# TIA_For_Photodiode.net
KiCad netlist of a schematic drawn in Altium Designer
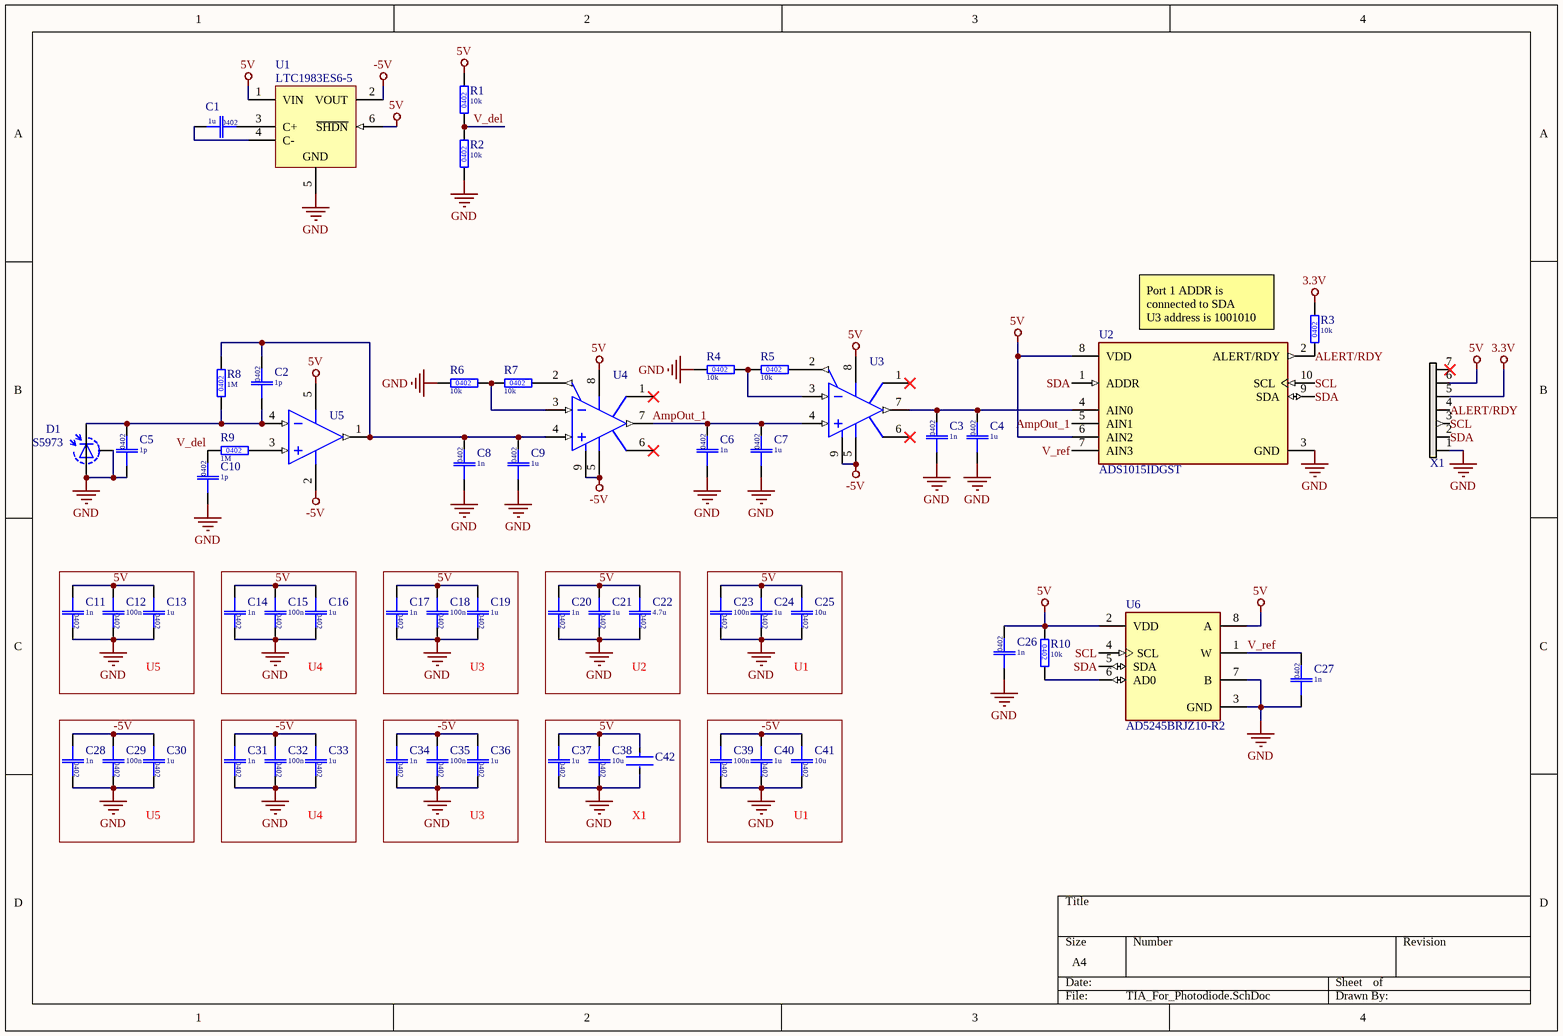
[diagram p0: TIA_For_Photodiode.SchDoc]

(export (version "E")
  (design (tool "Eeschema 10.0.6"))
  (components
    (comp (ref "C1")
      (value "1u")
      (footprint "SMD 0402")
      (fields (field (name "TOLERANCE") "10%") (field (name "VOLTAGE") "25v"))
      (libsource (lib "ComponentsDatabase") (part "Capacitor 0402"))
    )
    (comp (ref "C2")
      (value "1p")
      (footprint "SMD 0402")
      (fields (field (name "TOLERANCE") "20%") (field (name "VOLTAGE") "6,3v"))
      (libsource (lib "ComponentsDatabase") (part "Capacitor 0402"))
    )
    (comp (ref "C3")
      (value "1n")
      (footprint "SMD 0402")
      (fields (field (name "TOLERANCE") "20%") (field (name "VOLTAGE") "6,3v"))
      (libsource (lib "ComponentsDatabase") (part "Capacitor 0402"))
    )
    (comp (ref "C4")
      (value "1u")
      (footprint "SMD 0402")
      (fields (field (name "TOLERANCE") "20%") (field (name "VOLTAGE") "6,3v"))
      (libsource (lib "ComponentsDatabase") (part "Capacitor 0402"))
    )
    (comp (ref "C5")
      (value "1p")
      (footprint "SMD 0402")
      (fields (field (name "TOLERANCE") "20%") (field (name "VOLTAGE") "6,3v"))
      (libsource (lib "ComponentsDatabase") (part "Capacitor 0402"))
    )
    (comp (ref "C6")
      (value "1n")
      (footprint "SMD 0402")
      (fields (field (name "TOLERANCE") "20%") (field (name "VOLTAGE") "6,3v"))
      (libsource (lib "ComponentsDatabase") (part "Capacitor 0402"))
    )
    (comp (ref "C7")
      (value "1u")
      (footprint "SMD 0402")
      (fields (field (name "TOLERANCE") "20%") (field (name "VOLTAGE") "6,3v"))
      (libsource (lib "ComponentsDatabase") (part "Capacitor 0402"))
    )
    (comp (ref "C8")
      (value "1n")
      (footprint "SMD 0402")
      (fields (field (name "TOLERANCE") "20%") (field (name "VOLTAGE") "6,3v"))
      (libsource (lib "ComponentsDatabase") (part "Capacitor 0402"))
    )
    (comp (ref "C9")
      (value "1u")
      (footprint "SMD 0402")
      (fields (field (name "TOLERANCE") "20%") (field (name "VOLTAGE") "6,3v"))
      (libsource (lib "ComponentsDatabase") (part "Capacitor 0402"))
    )
    (comp (ref "C10")
      (value "1p")
      (footprint "SMD 0402")
      (fields (field (name "TOLERANCE") "20%") (field (name "VOLTAGE") "6,3v"))
      (libsource (lib "ComponentsDatabase") (part "Capacitor 0402"))
    )
    (comp (ref "C11")
      (value "1n")
      (footprint "SMD 0402")
      (fields (field (name "TOLERANCE") "20%") (field (name "VOLTAGE") "6,3v"))
      (libsource (lib "ComponentsDatabase") (part "Capacitor 0402"))
    )
    (comp (ref "C12")
      (value "100n")
      (footprint "SMD 0402")
      (fields (field (name "TOLERANCE") "20%") (field (name "VOLTAGE") "6,3v"))
      (libsource (lib "ComponentsDatabase") (part "Capacitor 0402"))
    )
    (comp (ref "C13")
      (value "1u")
      (footprint "SMD 0402")
      (fields (field (name "TOLERANCE") "20%") (field (name "VOLTAGE") "6,3v"))
      (libsource (lib "ComponentsDatabase") (part "Capacitor 0402"))
    )
    (comp (ref "C14")
      (value "1n")
      (footprint "SMD 0402")
      (fields (field (name "TOLERANCE") "20%") (field (name "VOLTAGE") "6,3v"))
      (libsource (lib "ComponentsDatabase") (part "Capacitor 0402"))
    )
    (comp (ref "C15")
      (value "100n")
      (footprint "SMD 0402")
      (fields (field (name "TOLERANCE") "20%") (field (name "VOLTAGE") "6,3v"))
      (libsource (lib "ComponentsDatabase") (part "Capacitor 0402"))
    )
    (comp (ref "C16")
      (value "1u")
      (footprint "SMD 0402")
      (fields (field (name "TOLERANCE") "20%") (field (name "VOLTAGE") "6,3v"))
      (libsource (lib "ComponentsDatabase") (part "Capacitor 0402"))
    )
    (comp (ref "C17")
      (value "1n")
      (footprint "SMD 0402")
      (fields (field (name "TOLERANCE") "20%") (field (name "VOLTAGE") "6,3v"))
      (libsource (lib "ComponentsDatabase") (part "Capacitor 0402"))
    )
    (comp (ref "C18")
      (value "100n")
      (footprint "SMD 0402")
      (fields (field (name "TOLERANCE") "20%") (field (name "VOLTAGE") "6,3v"))
      (libsource (lib "ComponentsDatabase") (part "Capacitor 0402"))
    )
    (comp (ref "C19")
      (value "1u")
      (footprint "SMD 0402")
      (fields (field (name "TOLERANCE") "20%") (field (name "VOLTAGE") "6,3v"))
      (libsource (lib "ComponentsDatabase") (part "Capacitor 0402"))
    )
    (comp (ref "C20")
      (value "1n")
      (footprint "SMD 0402")
      (fields (field (name "TOLERANCE") "20%") (field (name "VOLTAGE") "6,3v"))
      (libsource (lib "ComponentsDatabase") (part "Capacitor 0402"))
    )
    (comp (ref "C21")
      (value "1u")
      (footprint "SMD 0402")
      (fields (field (name "TOLERANCE") "20%") (field (name "VOLTAGE") "6,3v"))
      (libsource (lib "ComponentsDatabase") (part "Capacitor 0402"))
    )
    (comp (ref "C22")
      (value "4.7u")
      (footprint "SMD 0402")
      (fields (field (name "TOLERANCE") "20%") (field (name "VOLTAGE") "6,3v"))
      (libsource (lib "ComponentsDatabase") (part "Capacitor 0402"))
    )
    (comp (ref "C23")
      (value "100n")
      (footprint "SMD 0402")
      (fields (field (name "TOLERANCE") "20%") (field (name "VOLTAGE") "6,3v"))
      (libsource (lib "ComponentsDatabase") (part "Capacitor 0402"))
    )
    (comp (ref "C24")
      (value "1u")
      (footprint "SMD 0402")
      (fields (field (name "TOLERANCE") "20%") (field (name "VOLTAGE") "6,3v"))
      (libsource (lib "ComponentsDatabase") (part "Capacitor 0402"))
    )
    (comp (ref "C25")
      (value "10u")
      (footprint "SMD 0402")
      (fields (field (name "TOLERANCE") "20%") (field (name "VOLTAGE") "6,3v"))
      (libsource (lib "ComponentsDatabase") (part "Capacitor 0402"))
    )
    (comp (ref "C26")
      (value "1n")
      (footprint "SMD 0402")
      (fields (field (name "TOLERANCE") "20%") (field (name "VOLTAGE") "6,3v"))
      (libsource (lib "ComponentsDatabase") (part "Capacitor 0402"))
    )
    (comp (ref "C27")
      (value "1n")
      (footprint "SMD 0402")
      (fields (field (name "TOLERANCE") "20%") (field (name "VOLTAGE") "6,3v"))
      (libsource (lib "ComponentsDatabase") (part "Capacitor 0402"))
    )
    (comp (ref "C28")
      (value "1n")
      (footprint "SMD 0402")
      (fields (field (name "TOLERANCE") "20%") (field (name "VOLTAGE") "6,3v"))
      (libsource (lib "ComponentsDatabase") (part "Capacitor 0402"))
    )
    (comp (ref "C29")
      (value "100n")
      (footprint "SMD 0402")
      (fields (field (name "TOLERANCE") "20%") (field (name "VOLTAGE") "6,3v"))
      (libsource (lib "ComponentsDatabase") (part "Capacitor 0402"))
    )
    (comp (ref "C30")
      (value "1u")
      (footprint "SMD 0402")
      (fields (field (name "TOLERANCE") "20%") (field (name "VOLTAGE") "6,3v"))
      (libsource (lib "ComponentsDatabase") (part "Capacitor 0402"))
    )
    (comp (ref "C31")
      (value "1n")
      (footprint "SMD 0402")
      (fields (field (name "TOLERANCE") "20%") (field (name "VOLTAGE") "6,3v"))
      (libsource (lib "ComponentsDatabase") (part "Capacitor 0402"))
    )
    (comp (ref "C32")
      (value "100n")
      (footprint "SMD 0402")
      (fields (field (name "TOLERANCE") "20%") (field (name "VOLTAGE") "6,3v"))
      (libsource (lib "ComponentsDatabase") (part "Capacitor 0402"))
    )
    (comp (ref "C33")
      (value "1u")
      (footprint "SMD 0402")
      (fields (field (name "TOLERANCE") "20%") (field (name "VOLTAGE") "6,3v"))
      (libsource (lib "ComponentsDatabase") (part "Capacitor 0402"))
    )
    (comp (ref "C34")
      (value "1n")
      (footprint "SMD 0402")
      (fields (field (name "TOLERANCE") "20%") (field (name "VOLTAGE") "6,3v"))
      (libsource (lib "ComponentsDatabase") (part "Capacitor 0402"))
    )
    (comp (ref "C35")
      (value "100n")
      (footprint "SMD 0402")
      (fields (field (name "TOLERANCE") "20%") (field (name "VOLTAGE") "6,3v"))
      (libsource (lib "ComponentsDatabase") (part "Capacitor 0402"))
    )
    (comp (ref "C36")
      (value "1u")
      (footprint "SMD 0402")
      (fields (field (name "TOLERANCE") "20%") (field (name "VOLTAGE") "6,3v"))
      (libsource (lib "ComponentsDatabase") (part "Capacitor 0402"))
    )
    (comp (ref "C37")
      (value "1u")
      (footprint "SMD 0402")
      (fields (field (name "TOLERANCE") "20%") (field (name "VOLTAGE") "6,3v"))
      (libsource (lib "ComponentsDatabase") (part "Capacitor 0402"))
    )
    (comp (ref "C38")
      (value "10u")
      (footprint "SMD 0402")
      (fields (field (name "TOLERANCE") "20%") (field (name "VOLTAGE") "6,3v"))
      (libsource (lib "ComponentsDatabase") (part "Capacitor 0402"))
    )
    (comp (ref "C39")
      (value "100n")
      (footprint "SMD 0402")
      (fields (field (name "TOLERANCE") "20%") (field (name "VOLTAGE") "6,3v"))
      (libsource (lib "ComponentsDatabase") (part "Capacitor 0402"))
    )
    (comp (ref "C40")
      (value "1u")
      (footprint "SMD 0402")
      (fields (field (name "TOLERANCE") "20%") (field (name "VOLTAGE") "6,3v"))
      (libsource (lib "ComponentsDatabase") (part "Capacitor 0402"))
    )
    (comp (ref "C41")
      (value "10u")
      (footprint "SMD 0402")
      (fields (field (name "TOLERANCE") "20%") (field (name "VOLTAGE") "6,3v"))
      (libsource (lib "ComponentsDatabase") (part "Capacitor 0402"))
    )
    (comp (ref "C42")
      (value "GRM32ER60J107ME20L")
      (footprint "FP-GRM32-0_3-MFG")
      (description "CAP CER 100UF 6.3V X5R 1210")
      (fields
        (field (name "OCTOPART") "https://octopart.com/grm32er60j107me20l-murata-197007")
        (field (name "3DS PART NUMBER") "220-00002")
      )
      (libsource (lib "Altium Content Vault") (part "11868f565c42a9108669ba33697ecf6"))
    )
    (comp (ref "D1")
      (value "S5973")
      (footprint "TO-18")
      (description "Hamamatsu, S5973 IR + Visible Light Si PIN Photodiode, Through Hole TO-18")
      (libsource (lib "ShematicLIB") (part "S5973"))
    )
    (comp (ref "R1")
      (value "10k")
      (footprint "SMD 0402")
      (fields (field (name "TOLERANCE") "1%"))
      (libsource (lib "ComponentsDatabase") (part "Resistor 0402"))
    )
    (comp (ref "R2")
      (value "10k")
      (footprint "SMD 0402")
      (fields (field (name "TOLERANCE") "1%"))
      (libsource (lib "ComponentsDatabase") (part "Resistor 0402"))
    )
    (comp (ref "R3")
      (value "10k")
      (footprint "SMD 0402")
      (fields (field (name "TOLERANCE") "1%"))
      (libsource (lib "ComponentsDatabase") (part "Resistor 0402"))
    )
    (comp (ref "R4")
      (value "10k")
      (footprint "SMD 0402")
      (fields (field (name "TOLERANCE") "1%"))
      (libsource (lib "ComponentsDatabase") (part "Resistor 0402"))
    )
    (comp (ref "R5")
      (value "10k")
      (footprint "SMD 0402")
      (fields (field (name "TOLERANCE") "1%"))
      (libsource (lib "ComponentsDatabase") (part "Resistor 0402"))
    )
    (comp (ref "R6")
      (value "10k")
      (footprint "SMD 0402")
      (fields (field (name "TOLERANCE") "1%"))
      (libsource (lib "ComponentsDatabase") (part "Resistor 0402"))
    )
    (comp (ref "R7")
      (value "10k")
      (footprint "SMD 0402")
      (fields (field (name "TOLERANCE") "1%"))
      (libsource (lib "ComponentsDatabase") (part "Resistor 0402"))
    )
    (comp (ref "R8")
      (value "1M")
      (footprint "SMD 0402")
      (fields (field (name "TOLERANCE") "1%"))
      (libsource (lib "ComponentsDatabase") (part "Resistor 0402"))
    )
    (comp (ref "R9")
      (value "1M")
      (footprint "SMD 0402")
      (fields (field (name "TOLERANCE") "1%"))
      (libsource (lib "ComponentsDatabase") (part "Resistor 0402"))
    )
    (comp (ref "R10")
      (value "10k")
      (footprint "SMD 0402")
      (fields (field (name "TOLERANCE") "1%"))
      (libsource (lib "ComponentsDatabase") (part "Resistor 0402"))
    )
    (comp (ref "U1")
      (value "LTC1983ES6-5")
      (footprint "LT-S6-6-TSOT-23_M")
      (fields (field (name "MANUFACTURER") "Linear Technology"))
      (libsource (lib "Altium Content Vault") (part "LT-LTC1983-S6-6"))
    )
    (comp (ref "U2")
      (value "ADS1015IDGST")
      (footprint "FP-DGS0010A-MFG")
      (description "IC ADC 12BIT SIGMA-DELTA 10VSSOP")
      (libsource (lib "Altium Content Vault") (part "0fb225032f4bd54fd540a872e776a50"))
    )
    (comp (ref "U3")
      (value "AD8045ACPZ-REEL7")
      (footprint "ADI-CP-8-2_N")
      (fields (field (name "GENERIC PART NUMBER") "AD8045") (field (name "MANUFACTURER") "Analog Devices"))
      (libsource (lib "Altium Content Vault") (part "ADI-AD8045-CP-8-2"))
    )
    (comp (ref "U4")
      (value "AD8045ACPZ-REEL7")
      (footprint "ADI-CP-8-2_N")
      (fields (field (name "GENERIC PART NUMBER") "AD8045") (field (name "MANUFACTURER") "Analog Devices"))
      (libsource (lib "Altium Content Vault") (part "ADI-AD8045-CP-8-2"))
    )
    (comp (ref "U5")
      (value "AD8065ARTZ-REEL7")
      (footprint "ADI-RJ-5_L")
      (fields (field (name "GENERIC PART NUMBER") "AD8065") (field (name "MANUFACTURER") "Analog Devices"))
      (libsource (lib "Altium Content Vault") (part "ADI-AD80XX-5"))
    )
    (comp (ref "U6")
      (value "AD5245BRJZ10-R2")
      (footprint "FP-RJ-8-IPC_C")
      (description "IC DGT POT 10KOHM 256TAP SOT23-8")
      (fields (field (name "TOLERANCE") "30%") (field (name "MANUFACTURER") "Analog Devices"))
      (libsource (lib "Altium Content Vault") (part "8d408c839f24318d0976f3536df8182"))
    )
    (comp (ref "X1")
      (value "PicoBlade 7 pins")
      (footprint "PicoBlade 7 pins")
      (libsource (lib "ShematicLIB") (part "PicoBlade 7 pins"))
    )
  )
  (nets
    (net (code "1") (name "-5V") (class "Default")
      (node (ref "C28") (pin "1") (pinfunction "1_1") (pintype "passive"))
      (node (ref "C29") (pin "1") (pinfunction "1_1") (pintype "passive"))
      (node (ref "C30") (pin "1") (pinfunction "1_1") (pintype "passive"))
      (node (ref "C31") (pin "1") (pinfunction "1_1") (pintype "passive"))
      (node (ref "C32") (pin "1") (pinfunction "1_1") (pintype "passive"))
      (node (ref "C33") (pin "1") (pinfunction "1_1") (pintype "passive"))
      (node (ref "C34") (pin "1") (pinfunction "1_1") (pintype "passive"))
      (node (ref "C35") (pin "1") (pinfunction "1_1") (pintype "passive"))
      (node (ref "C36") (pin "1") (pinfunction "1_1") (pintype "passive"))
      (node (ref "C39") (pin "1") (pinfunction "1_1") (pintype "passive"))
      (node (ref "C40") (pin "1") (pinfunction "1_1") (pintype "passive"))
      (node (ref "C41") (pin "1") (pinfunction "1_1") (pintype "passive"))
      (node (ref "U1") (pin "2") (pinfunction "VOUT_2") (pintype "power_in"))
      (node (ref "U3") (pin "5") (pinfunction "-VS_5") (pintype "power_in"))
      (node (ref "U3") (pin "9") (pinfunction "EP_9") (pintype "power_in"))
      (node (ref "U4") (pin "5") (pinfunction "-VS_5") (pintype "power_in"))
      (node (ref "U4") (pin "9") (pinfunction "EP_9") (pintype "power_in"))
      (node (ref "U5") (pin "2") (pinfunction "-VS_2") (pintype "power_in"))
    )
    (net (code "2") (name "/ALERT{slash}RDY") (class "Default")
      (node (ref "R3") (pin "1") (pinfunction "1_1") (pintype "passive"))
      (node (ref "U2") (pin "2") (pinfunction "ALERT/RDY_2") (pintype "output"))
      (node (ref "X1") (pin "4") (pinfunction "4_4") (pintype "passive"))
    )
    (net (code "3") (name "/AmpOut_1") (class "Default")
      (node (ref "C6") (pin "2") (pinfunction "2_2") (pintype "passive"))
      (node (ref "C7") (pin "2") (pinfunction "2_2") (pintype "passive"))
      (node (ref "U2") (pin "5") (pinfunction "AIN1_5") (pintype "passive"))
      (node (ref "U3") (pin "4") (pinfunction "+IN_4") (pintype "input"))
      (node (ref "U4") (pin "7") (pinfunction "OUT_7") (pintype "output"))
    )
    (net (code "4") (name "/SCL") (class "Default")
      (node (ref "U2") (pin "10") (pinfunction "SCL_10") (pintype "input"))
      (node (ref "U6") (pin "4") (pinfunction "SCL_4") (pintype "input"))
      (node (ref "X1") (pin "3") (pinfunction "3_3") (pintype "output"))
    )
    (net (code "5") (name "/SDA") (class "Default")
      (node (ref "U2") (pin "1") (pinfunction "ADDR_1") (pintype "input"))
      (node (ref "U2") (pin "9") (pinfunction "SDA_9") (pintype "bidirectional"))
      (node (ref "U6") (pin "5") (pinfunction "SDA_5") (pintype "bidirectional"))
      (node (ref "X1") (pin "2") (pinfunction "2_2") (pintype "passive"))
    )
    (net (code "6") (name "/V_del") (class "Default")
      (node (ref "C10") (pin "2") (pinfunction "2_2") (pintype "passive"))
      (node (ref "R1") (pin "1") (pinfunction "1_1") (pintype "passive"))
      (node (ref "R2") (pin "2") (pinfunction "2_2") (pintype "passive"))
      (node (ref "R9") (pin "1") (pinfunction "1_1") (pintype "passive"))
    )
    (net (code "7") (name "/V_ref") (class "Default")
      (node (ref "C27") (pin "2") (pinfunction "2_2") (pintype "passive"))
      (node (ref "U2") (pin "7") (pinfunction "AIN3_7") (pintype "passive"))
      (node (ref "U6") (pin "1") (pinfunction "W_1") (pintype "passive"))
    )
    (net (code "8") (name "3.3V") (class "Default")
      (node (ref "R3") (pin "2") (pinfunction "2_2") (pintype "passive"))
      (node (ref "X1") (pin "5") (pinfunction "5_5") (pintype "passive"))
    )
    (net (code "9") (name "5V") (class "Default")
      (node (ref "C11") (pin "1") (pinfunction "1_1") (pintype "passive"))
      (node (ref "C12") (pin "1") (pinfunction "1_1") (pintype "passive"))
      (node (ref "C13") (pin "1") (pinfunction "1_1") (pintype "passive"))
      (node (ref "C14") (pin "1") (pinfunction "1_1") (pintype "passive"))
      (node (ref "C15") (pin "1") (pinfunction "1_1") (pintype "passive"))
      (node (ref "C16") (pin "1") (pinfunction "1_1") (pintype "passive"))
      (node (ref "C17") (pin "1") (pinfunction "1_1") (pintype "passive"))
      (node (ref "C18") (pin "1") (pinfunction "1_1") (pintype "passive"))
      (node (ref "C19") (pin "1") (pinfunction "1_1") (pintype "passive"))
      (node (ref "C20") (pin "1") (pinfunction "1_1") (pintype "passive"))
      (node (ref "C21") (pin "1") (pinfunction "1_1") (pintype "passive"))
      (node (ref "C22") (pin "1") (pinfunction "1_1") (pintype "passive"))
      (node (ref "C23") (pin "1") (pinfunction "1_1") (pintype "passive"))
      (node (ref "C24") (pin "1") (pinfunction "1_1") (pintype "passive"))
      (node (ref "C25") (pin "1") (pinfunction "1_1") (pintype "passive"))
      (node (ref "C26") (pin "2") (pinfunction "2_2") (pintype "passive"))
      (node (ref "C37") (pin "1") (pinfunction "1_1") (pintype "passive"))
      (node (ref "C38") (pin "1") (pinfunction "1_1") (pintype "passive"))
      (node (ref "C42") (pin "1") (pinfunction "1_1") (pintype "passive"))
      (node (ref "R1") (pin "2") (pinfunction "2_2") (pintype "passive"))
      (node (ref "R10") (pin "1") (pinfunction "1_1") (pintype "passive"))
      (node (ref "U1") (pin "1") (pinfunction "VIN_1") (pintype "power_in"))
      (node (ref "U1") (pin "6") (pinfunction "~{SHDN}_6") (pintype "input"))
      (node (ref "U2") (pin "6") (pinfunction "AIN2_6") (pintype "passive"))
      (node (ref "U2") (pin "8") (pinfunction "VDD_8") (pintype "power_in"))
      (node (ref "U3") (pin "8") (pinfunction "+VS_8") (pintype "power_in"))
      (node (ref "U4") (pin "8") (pinfunction "+VS_8") (pintype "power_in"))
      (node (ref "U5") (pin "5") (pinfunction "+VS_5") (pintype "power_in"))
      (node (ref "U6") (pin "2") (pinfunction "VDD_2") (pintype "power_in"))
      (node (ref "U6") (pin "8") (pinfunction "A_8") (pintype "passive"))
      (node (ref "X1") (pin "6") (pinfunction "6_6") (pintype "passive"))
    )
    (net (code "10") (name "GND") (class "Default")
      (node (ref "C10") (pin "1") (pinfunction "1_1") (pintype "passive"))
      (node (ref "C11") (pin "2") (pinfunction "2_2") (pintype "passive"))
      (node (ref "C12") (pin "2") (pinfunction "2_2") (pintype "passive"))
      (node (ref "C13") (pin "2") (pinfunction "2_2") (pintype "passive"))
      (node (ref "C14") (pin "2") (pinfunction "2_2") (pintype "passive"))
      (node (ref "C15") (pin "2") (pinfunction "2_2") (pintype "passive"))
      (node (ref "C16") (pin "2") (pinfunction "2_2") (pintype "passive"))
      (node (ref "C17") (pin "2") (pinfunction "2_2") (pintype "passive"))
      (node (ref "C18") (pin "2") (pinfunction "2_2") (pintype "passive"))
      (node (ref "C19") (pin "2") (pinfunction "2_2") (pintype "passive"))
      (node (ref "C20") (pin "2") (pinfunction "2_2") (pintype "passive"))
      (node (ref "C21") (pin "2") (pinfunction "2_2") (pintype "passive"))
      (node (ref "C22") (pin "2") (pinfunction "2_2") (pintype "passive"))
      (node (ref "C23") (pin "2") (pinfunction "2_2") (pintype "passive"))
      (node (ref "C24") (pin "2") (pinfunction "2_2") (pintype "passive"))
      (node (ref "C25") (pin "2") (pinfunction "2_2") (pintype "passive"))
      (node (ref "C26") (pin "1") (pinfunction "1_1") (pintype "passive"))
      (node (ref "C27") (pin "1") (pinfunction "1_1") (pintype "passive"))
      (node (ref "C28") (pin "2") (pinfunction "2_2") (pintype "passive"))
      (node (ref "C29") (pin "2") (pinfunction "2_2") (pintype "passive"))
      (node (ref "C3") (pin "1") (pinfunction "1_1") (pintype "passive"))
      (node (ref "C30") (pin "2") (pinfunction "2_2") (pintype "passive"))
      (node (ref "C31") (pin "2") (pinfunction "2_2") (pintype "passive"))
      (node (ref "C32") (pin "2") (pinfunction "2_2") (pintype "passive"))
      (node (ref "C33") (pin "2") (pinfunction "2_2") (pintype "passive"))
      (node (ref "C34") (pin "2") (pinfunction "2_2") (pintype "passive"))
      (node (ref "C35") (pin "2") (pinfunction "2_2") (pintype "passive"))
      (node (ref "C36") (pin "2") (pinfunction "2_2") (pintype "passive"))
      (node (ref "C37") (pin "2") (pinfunction "2_2") (pintype "passive"))
      (node (ref "C38") (pin "2") (pinfunction "2_2") (pintype "passive"))
      (node (ref "C39") (pin "2") (pinfunction "2_2") (pintype "passive"))
      (node (ref "C4") (pin "1") (pinfunction "1_1") (pintype "passive"))
      (node (ref "C40") (pin "2") (pinfunction "2_2") (pintype "passive"))
      (node (ref "C41") (pin "2") (pinfunction "2_2") (pintype "passive"))
      (node (ref "C42") (pin "2") (pinfunction "2_2") (pintype "passive"))
      (node (ref "C5") (pin "1") (pinfunction "1_1") (pintype "passive"))
      (node (ref "C6") (pin "1") (pinfunction "1_1") (pintype "passive"))
      (node (ref "C7") (pin "1") (pinfunction "1_1") (pintype "passive"))
      (node (ref "C8") (pin "1") (pinfunction "1_1") (pintype "passive"))
      (node (ref "C9") (pin "1") (pinfunction "1_1") (pintype "passive"))
      (node (ref "D1") (pin "2") (pinfunction "S_2") (pintype "passive"))
      (node (ref "D1") (pin "3") (pinfunction "A_3") (pintype "passive"))
      (node (ref "R2") (pin "1") (pinfunction "1_1") (pintype "passive"))
      (node (ref "R4") (pin "1") (pinfunction "1_1") (pintype "passive"))
      (node (ref "R6") (pin "1") (pinfunction "1_1") (pintype "passive"))
      (node (ref "U1") (pin "5") (pinfunction "GND_5") (pintype "power_in"))
      (node (ref "U2") (pin "3") (pinfunction "GND_3") (pintype "power_in"))
      (node (ref "U6") (pin "3") (pinfunction "GND_3") (pintype "power_in"))
      (node (ref "U6") (pin "7") (pinfunction "B_7") (pintype "passive"))
      (node (ref "X1") (pin "1") (pinfunction "1_1") (pintype "passive"))
    )
    (net (code "11") (name "Net-(D1-C)") (class "Default")
      (node (ref "C2") (pin "1") (pinfunction "1_1") (pintype "passive"))
      (node (ref "C5") (pin "2") (pinfunction "2_2") (pintype "passive"))
      (node (ref "D1") (pin "1") (pinfunction "C_1") (pintype "passive"))
      (node (ref "R8") (pin "1") (pinfunction "1_1") (pintype "passive"))
      (node (ref "U5") (pin "4") (pinfunction "-IN_4") (pintype "input"))
    )
    (net (code "12") (name "Net-(U1-C+)") (class "Default")
      (node (ref "C1") (pin "2") (pinfunction "2_2") (pintype "passive"))
      (node (ref "U1") (pin "3") (pinfunction "C+_3") (pintype "passive"))
    )
    (net (code "13") (name "Net-(U1-C-)") (class "Default")
      (node (ref "C1") (pin "1") (pinfunction "1_1") (pintype "passive"))
      (node (ref "U1") (pin "4") (pinfunction "C-_4") (pintype "passive"))
    )
    (net (code "14") (name "Net-(U2-AIN0)") (class "Default")
      (node (ref "C3") (pin "2") (pinfunction "2_2") (pintype "passive"))
      (node (ref "C4") (pin "2") (pinfunction "2_2") (pintype "passive"))
      (node (ref "U2") (pin "4") (pinfunction "AIN0_4") (pintype "passive"))
      (node (ref "U3") (pin "7") (pinfunction "OUT_7") (pintype "output"))
    )
    (net (code "15") (name "Net-(U3--IN)") (class "Default")
      (node (ref "R4") (pin "2") (pinfunction "2_2") (pintype "passive"))
      (node (ref "R5") (pin "1") (pinfunction "1_1") (pintype "passive"))
      (node (ref "U3") (pin "3") (pinfunction "-IN_3") (pintype "input"))
    )
    (net (code "16") (name "Net-(U3-FEEDBACK)") (class "Default")
      (node (ref "R5") (pin "2") (pinfunction "2_2") (pintype "passive"))
      (node (ref "U3") (pin "2") (pinfunction "FEEDBACK_2") (pintype "output"))
    )
    (net (code "17") (name "Net-(U4-+IN)") (class "Default")
      (node (ref "C2") (pin "2") (pinfunction "2_2") (pintype "passive"))
      (node (ref "C8") (pin "2") (pinfunction "2_2") (pintype "passive"))
      (node (ref "C9") (pin "2") (pinfunction "2_2") (pintype "passive"))
      (node (ref "R8") (pin "2") (pinfunction "2_2") (pintype "passive"))
      (node (ref "U4") (pin "4") (pinfunction "+IN_4") (pintype "input"))
      (node (ref "U5") (pin "1") (pinfunction "VOUT_1") (pintype "output"))
    )
    (net (code "18") (name "Net-(U4--IN)") (class "Default")
      (node (ref "R6") (pin "2") (pinfunction "2_2") (pintype "passive"))
      (node (ref "R7") (pin "1") (pinfunction "1_1") (pintype "passive"))
      (node (ref "U4") (pin "3") (pinfunction "-IN_3") (pintype "input"))
    )
    (net (code "19") (name "Net-(U4-FEEDBACK)") (class "Default")
      (node (ref "R7") (pin "2") (pinfunction "2_2") (pintype "passive"))
      (node (ref "U4") (pin "2") (pinfunction "FEEDBACK_2") (pintype "output"))
    )
    (net (code "20") (name "Net-(U5-+IN)") (class "Default")
      (node (ref "R9") (pin "2") (pinfunction "2_2") (pintype "passive"))
      (node (ref "U5") (pin "3") (pinfunction "+IN_3") (pintype "input"))
    )
    (net (code "21") (name "Net-(U6-AD0)") (class "Default")
      (node (ref "R10") (pin "2") (pinfunction "2_2") (pintype "passive"))
      (node (ref "U6") (pin "6") (pinfunction "AD0_6") (pintype "bidirectional"))
    )
    (net (code "22") (name "unconnected-(U3-NC-Pad1)") (class "Default")
      (node (ref "U3") (pin "1") (pinfunction "NC_1") (pintype "passive+no_connect"))
    )
    (net (code "23") (name "unconnected-(U3-NC-Pad6)") (class "Default")
      (node (ref "U3") (pin "6") (pinfunction "NC_6") (pintype "passive+no_connect"))
    )
    (net (code "24") (name "unconnected-(U4-NC-Pad1)") (class "Default")
      (node (ref "U4") (pin "1") (pinfunction "NC_1") (pintype "passive+no_connect"))
    )
    (net (code "25") (name "unconnected-(U4-NC-Pad6)") (class "Default")
      (node (ref "U4") (pin "6") (pinfunction "NC_6") (pintype "passive+no_connect"))
    )
    (net (code "26") (name "unconnected-(X1-Pad7)") (class "Default")
      (node (ref "X1") (pin "7") (pinfunction "7_7") (pintype "passive+no_connect"))
    )
  )
)
